# flower.net
KiCad netlist of a schematic drawn in EAGLE
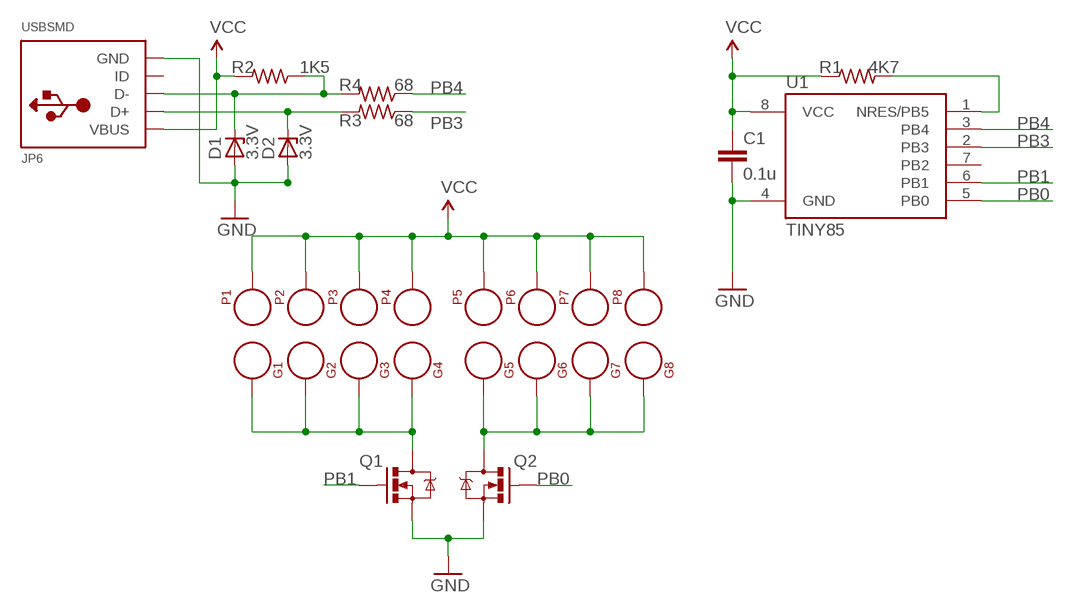
[diagram p0: schematic, sheet 1]

(export (version "E")
  (design (tool "Eeschema 10.0.6"))
  (components
    (comp (ref "C1")
      (value "0.1u")
      (footprint "eagle-import:C025-025X050")
      (libsource (lib "eagle-import") (part "C-EU025-025X050"))
    )
    (comp (ref "D1")
      (value "3.3V")
      (footprint "eagle-import:ZDIO-5")
      (libsource (lib "eagle-import") (part "ZENER-DIODEZD-5"))
    )
    (comp (ref "D2")
      (value "3.3V")
      (footprint "eagle-import:ZDIO-5")
      (libsource (lib "eagle-import") (part "ZENER-DIODEZD-5"))
    )
    (comp (ref "G1")
      (value "SEW_HOLE")
      (footprint "eagle-import:SIMPLE_HOLE")
      (libsource (lib "eagle-import") (part "SEW_HOLE"))
    )
    (comp (ref "G2")
      (value "SEW_HOLE")
      (footprint "eagle-import:SIMPLE_HOLE")
      (libsource (lib "eagle-import") (part "SEW_HOLE"))
    )
    (comp (ref "G3")
      (value "SEW_HOLE")
      (footprint "eagle-import:SIMPLE_HOLE")
      (libsource (lib "eagle-import") (part "SEW_HOLE"))
    )
    (comp (ref "G4")
      (value "SEW_HOLE")
      (footprint "eagle-import:SIMPLE_HOLE")
      (libsource (lib "eagle-import") (part "SEW_HOLE"))
    )
    (comp (ref "G5")
      (value "SEW_HOLE")
      (footprint "eagle-import:SIMPLE_HOLE")
      (libsource (lib "eagle-import") (part "SEW_HOLE"))
    )
    (comp (ref "G6")
      (value "SEW_HOLE")
      (footprint "eagle-import:SIMPLE_HOLE")
      (libsource (lib "eagle-import") (part "SEW_HOLE"))
    )
    (comp (ref "G7")
      (value "SEW_HOLE")
      (footprint "eagle-import:SIMPLE_HOLE")
      (libsource (lib "eagle-import") (part "SEW_HOLE"))
    )
    (comp (ref "G8")
      (value "SEW_HOLE")
      (footprint "eagle-import:SIMPLE_HOLE")
      (libsource (lib "eagle-import") (part "SEW_HOLE"))
    )
    (comp (ref "JP6")
      (value "USBSMD")
      (footprint "eagle-import:USB-MINIB-THM-MOLEX")
      (libsource (lib "eagle-import") (part "USBMOLEX"))
    )
    (comp (ref "P1")
      (value "SEW_HOLE")
      (footprint "eagle-import:SIMPLE_HOLE")
      (libsource (lib "eagle-import") (part "SEW_HOLE"))
    )
    (comp (ref "P2")
      (value "SEW_HOLE")
      (footprint "eagle-import:SIMPLE_HOLE")
      (libsource (lib "eagle-import") (part "SEW_HOLE"))
    )
    (comp (ref "P3")
      (value "SEW_HOLE")
      (footprint "eagle-import:SIMPLE_HOLE")
      (libsource (lib "eagle-import") (part "SEW_HOLE"))
    )
    (comp (ref "P4")
      (value "SEW_HOLE")
      (footprint "eagle-import:SIMPLE_HOLE")
      (libsource (lib "eagle-import") (part "SEW_HOLE"))
    )
    (comp (ref "P5")
      (value "SEW_HOLE")
      (footprint "eagle-import:SIMPLE_HOLE")
      (libsource (lib "eagle-import") (part "SEW_HOLE"))
    )
    (comp (ref "P6")
      (value "SEW_HOLE")
      (footprint "eagle-import:SIMPLE_HOLE")
      (libsource (lib "eagle-import") (part "SEW_HOLE"))
    )
    (comp (ref "P7")
      (value "SEW_HOLE")
      (footprint "eagle-import:SIMPLE_HOLE")
      (libsource (lib "eagle-import") (part "SEW_HOLE"))
    )
    (comp (ref "P8")
      (value "SEW_HOLE")
      (footprint "eagle-import:SIMPLE_HOLE")
      (libsource (lib "eagle-import") (part "SEW_HOLE"))
    )
    (comp (ref "Q1")
      (value "2N7000")
      (footprint "eagle-import:TO-92")
      (libsource (lib "eagle-import") (part "MOSFET-NCHANNEL2N7000"))
    )
    (comp (ref "Q2")
      (value "2N7000")
      (footprint "eagle-import:TO-92")
      (libsource (lib "eagle-import") (part "MOSFET-NCHANNEL2N7000"))
    )
    (comp (ref "R1")
      (value "4K7")
      (footprint "eagle-import:0204_7")
      (libsource (lib "eagle-import") (part "R-US_0204/7"))
    )
    (comp (ref "R2")
      (value "1K5")
      (footprint "eagle-import:0204_7")
      (libsource (lib "eagle-import") (part "R-US_0204/7"))
    )
    (comp (ref "R3")
      (value "68")
      (footprint "eagle-import:0204_7")
      (libsource (lib "eagle-import") (part "R-US_0204/7"))
    )
    (comp (ref "R4")
      (value "68")
      (footprint "eagle-import:0204_7")
      (libsource (lib "eagle-import") (part "R-US_0204/7"))
    )
    (comp (ref "U1")
      (value "TINY85")
      (footprint "eagle-import:PDIP08_300MIL")
      (libsource (lib "eagle-import") (part "ATTINY85P-"))
    )
  )
  (nets
    (net (code "1") (name "/PB0") (class "Default")
      (node (ref "Q2") (pin "2") (pinfunction "G_2") (pintype "passive"))
      (node (ref "U1") (pin "5") (pinfunction "PB0_5") (pintype "bidirectional"))
    )
    (net (code "2") (name "/PB1") (class "Default")
      (node (ref "Q1") (pin "2") (pinfunction "G_2") (pintype "passive"))
      (node (ref "U1") (pin "6") (pinfunction "PB1_6") (pintype "bidirectional"))
    )
    (net (code "3") (name "/PB3") (class "Default")
      (node (ref "R4") (pin "1") (pinfunction "1_1") (pintype "passive"))
      (node (ref "U1") (pin "2") (pinfunction "PB3_2") (pintype "bidirectional"))
    )
    (net (code "4") (name "/PB4") (class "Default")
      (node (ref "R3") (pin "1") (pinfunction "1_1") (pintype "passive"))
      (node (ref "U1") (pin "3") (pinfunction "PB4_3") (pintype "bidirectional"))
    )
    (net (code "5") (name "GND") (class "Default")
      (node (ref "C1") (pin "2") (pinfunction "2_2") (pintype "passive"))
      (node (ref "D1") (pin "A") (pinfunction "A_A") (pintype "passive"))
      (node (ref "D2") (pin "A") (pinfunction "A_A") (pintype "passive"))
      (node (ref "JP6") (pin "GND") (pinfunction "GND_GND") (pintype "power_in"))
      (node (ref "Q1") (pin "1") (pinfunction "S_1") (pintype "passive"))
      (node (ref "Q2") (pin "1") (pinfunction "S_1") (pintype "passive"))
      (node (ref "U1") (pin "4") (pinfunction "GND_4") (pintype "power_in"))
    )
    (net (code "6") (name "Net-(D1-PadC)") (class "Default")
      (node (ref "D1") (pin "C") (pinfunction "C_C") (pintype "passive"))
      (node (ref "JP6") (pin "D-") (pinfunction "D-_D-") (pintype "bidirectional"))
      (node (ref "R2") (pin "1") (pinfunction "1_1") (pintype "passive"))
      (node (ref "R4") (pin "2") (pinfunction "2_2") (pintype "passive"))
    )
    (net (code "7") (name "Net-(D2-PadC)") (class "Default")
      (node (ref "D2") (pin "C") (pinfunction "C_C") (pintype "passive"))
      (node (ref "JP6") (pin "D+") (pinfunction "D+_D+") (pintype "bidirectional"))
      (node (ref "R3") (pin "2") (pinfunction "2_2") (pintype "passive"))
    )
    (net (code "8") (name "Net-(Q1-D)") (class "Default")
      (node (ref "G1") (pin "P$1") (pinfunction "P$1_P$1") (pintype "bidirectional"))
      (node (ref "G2") (pin "P$1") (pinfunction "P$1_P$1") (pintype "bidirectional"))
      (node (ref "G3") (pin "P$1") (pinfunction "P$1_P$1") (pintype "bidirectional"))
      (node (ref "G4") (pin "P$1") (pinfunction "P$1_P$1") (pintype "bidirectional"))
      (node (ref "Q1") (pin "3") (pinfunction "D_3") (pintype "passive"))
    )
    (net (code "9") (name "Net-(Q2-D)") (class "Default")
      (node (ref "G5") (pin "P$1") (pinfunction "P$1_P$1") (pintype "bidirectional"))
      (node (ref "G6") (pin "P$1") (pinfunction "P$1_P$1") (pintype "bidirectional"))
      (node (ref "G7") (pin "P$1") (pinfunction "P$1_P$1") (pintype "bidirectional"))
      (node (ref "G8") (pin "P$1") (pinfunction "P$1_P$1") (pintype "bidirectional"))
      (node (ref "Q2") (pin "3") (pinfunction "D_3") (pintype "passive"))
    )
    (net (code "10") (name "Net-(U1-NRES{slash}PB5)") (class "Default")
      (node (ref "R1") (pin "2") (pinfunction "2_2") (pintype "passive"))
      (node (ref "U1") (pin "1") (pinfunction "NRES/PB5_1") (pintype "bidirectional"))
    )
    (net (code "11") (name "VCC") (class "Default")
      (node (ref "C1") (pin "1") (pinfunction "1_1") (pintype "passive"))
      (node (ref "JP6") (pin "VBUS") (pinfunction "VBUS_VBUS") (pintype "power_in"))
      (node (ref "P1") (pin "P$1") (pinfunction "P$1_P$1") (pintype "bidirectional"))
      (node (ref "P2") (pin "P$1") (pinfunction "P$1_P$1") (pintype "bidirectional"))
      (node (ref "P3") (pin "P$1") (pinfunction "P$1_P$1") (pintype "bidirectional"))
      (node (ref "P4") (pin "P$1") (pinfunction "P$1_P$1") (pintype "bidirectional"))
      (node (ref "P5") (pin "P$1") (pinfunction "P$1_P$1") (pintype "bidirectional"))
      (node (ref "P6") (pin "P$1") (pinfunction "P$1_P$1") (pintype "bidirectional"))
      (node (ref "P7") (pin "P$1") (pinfunction "P$1_P$1") (pintype "bidirectional"))
      (node (ref "P8") (pin "P$1") (pinfunction "P$1_P$1") (pintype "bidirectional"))
      (node (ref "R1") (pin "1") (pinfunction "1_1") (pintype "passive"))
      (node (ref "R2") (pin "2") (pinfunction "2_2") (pintype "passive"))
      (node (ref "U1") (pin "8") (pinfunction "VCC_8") (pintype "power_in"))
    )
    (net (code "12") (name "unconnected-(JP6-PadID)") (class "Default")
      (node (ref "JP6") (pin "ID") (pinfunction "ID_ID") (pintype "bidirectional"))
    )
    (net (code "13") (name "unconnected-(U1-PB2-Pad7)") (class "Default")
      (node (ref "U1") (pin "7") (pinfunction "PB2_7") (pintype "bidirectional"))
    )
  )
)
